# Rudder_-_Prototype_1.net
KiCad netlist of a schematic drawn in EAGLE
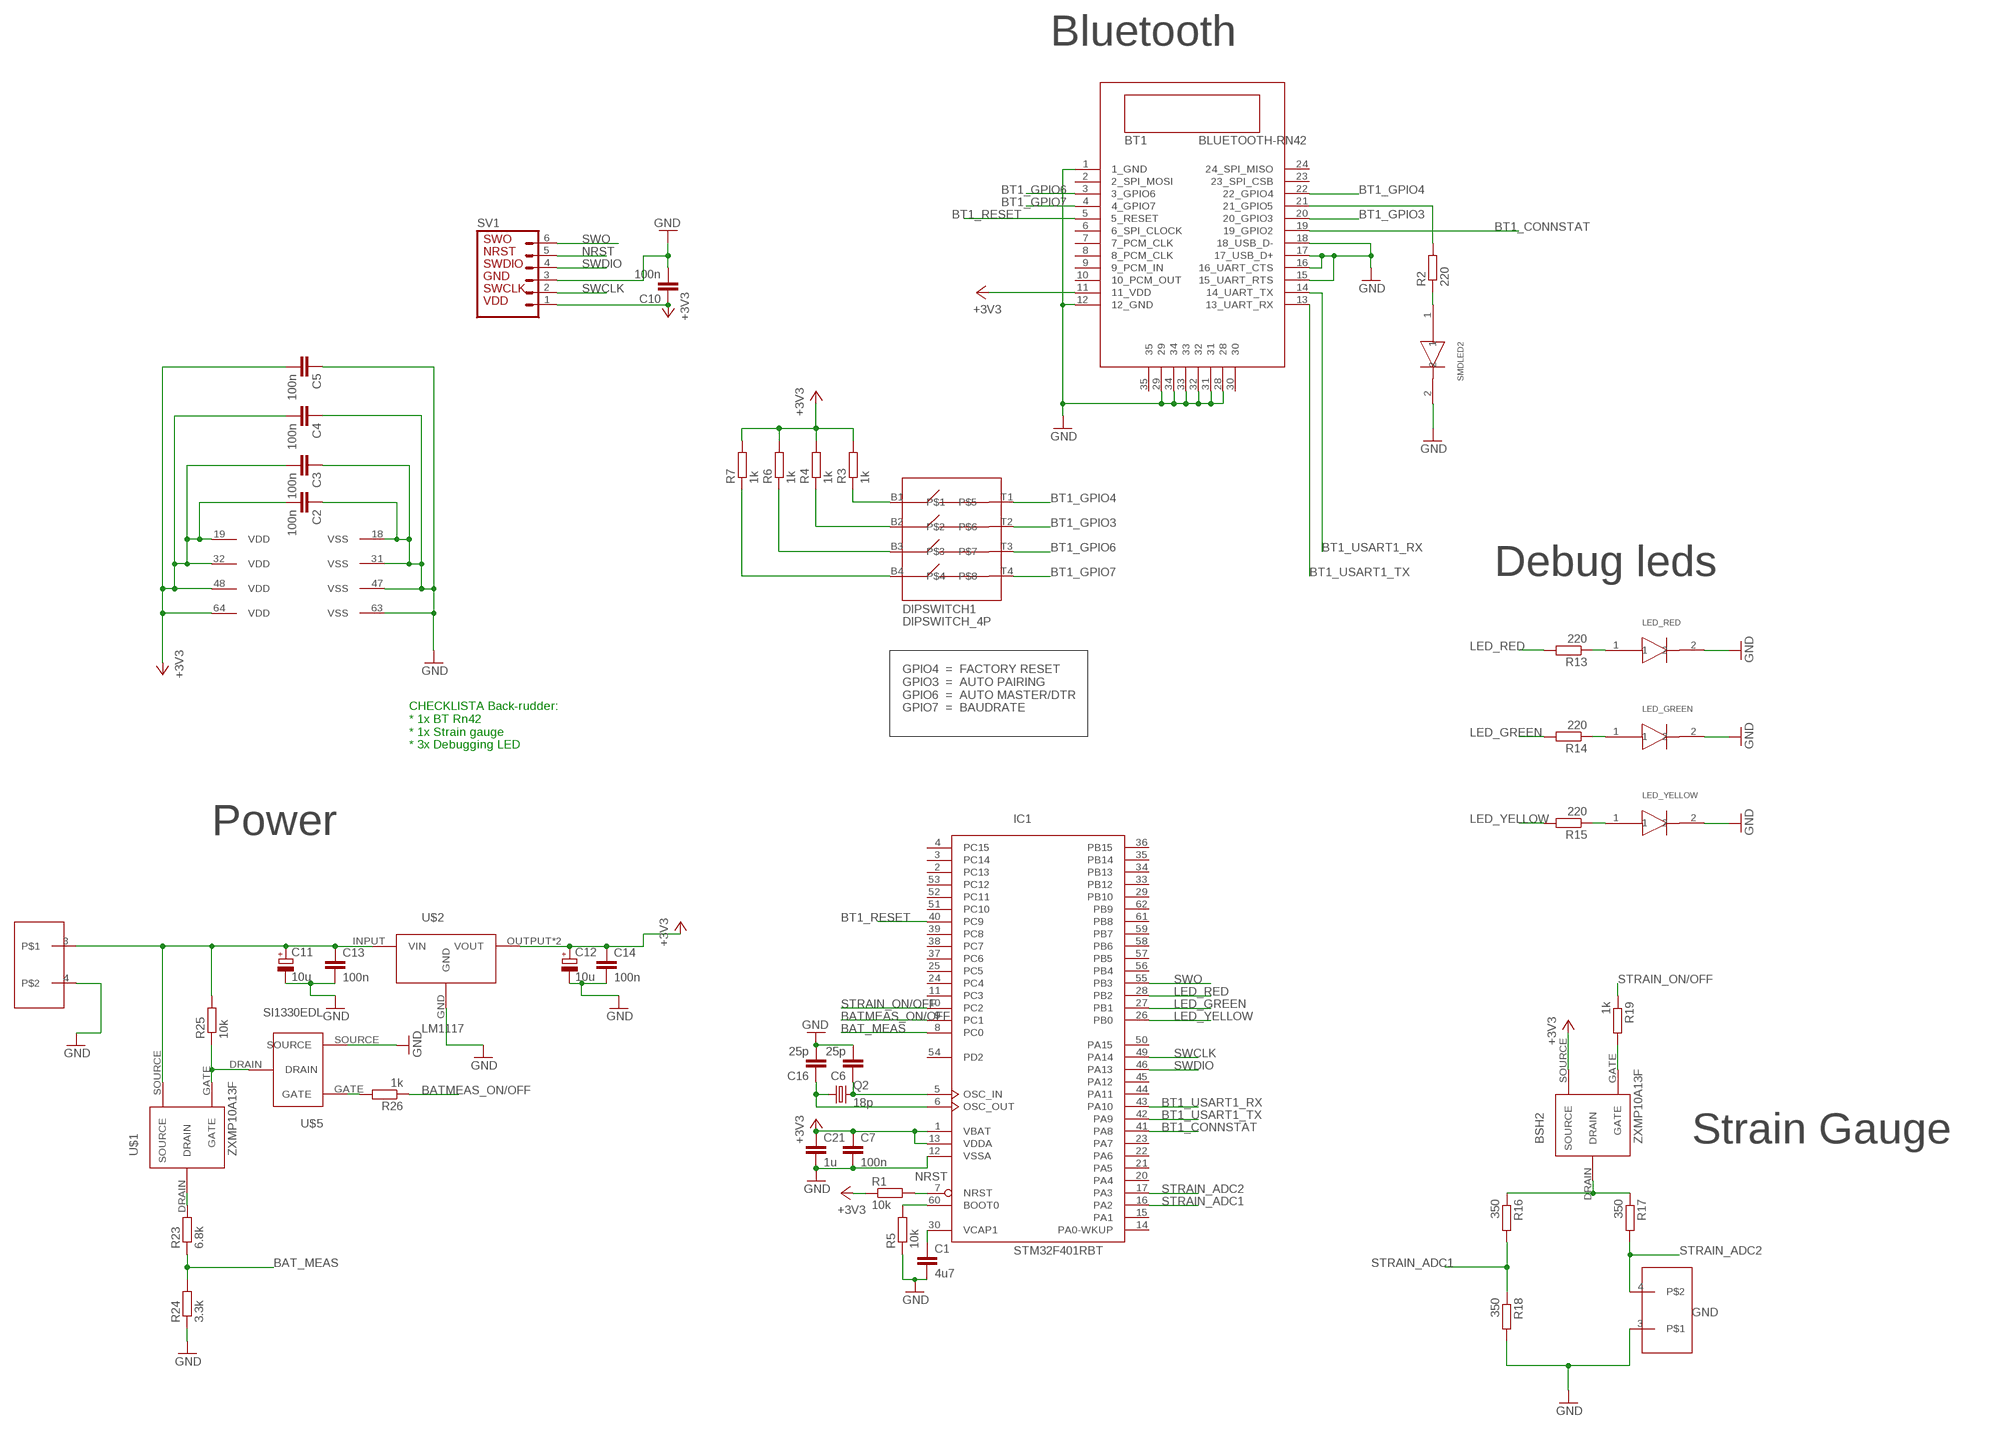
[diagram p0: schematic, sheet 1]

(export (version "E")
  (design (tool "Eeschema 10.0.6"))
  (components
    (comp (ref "BSH2")
      (value "ZXMP10A13F")
      (footprint "eagle-import:P-CHANNEL")
      (libsource (lib "eagle-import") (part "ZXMP10A13F"))
    )
    (comp (ref "BT1")
      (value "BLUETOOTH-RN42")
      (footprint "eagle-import:RN42")
      (libsource (lib "eagle-import") (part "BLUETOOTH-RN42"))
    )
    (comp (ref "C1")
      (value "4u7")
      (footprint "eagle-import:C0805")
      (libsource (lib "eagle-import") (part "C-EUC0805"))
    )
    (comp (ref "C2")
      (value "100n")
      (footprint "eagle-import:C0805")
      (libsource (lib "eagle-import") (part "C-EUC0805"))
    )
    (comp (ref "C3")
      (value "100n")
      (footprint "eagle-import:C0805")
      (libsource (lib "eagle-import") (part "C-EUC0805"))
    )
    (comp (ref "C4")
      (value "100n")
      (footprint "eagle-import:C0805")
      (libsource (lib "eagle-import") (part "C-EUC0805"))
    )
    (comp (ref "C5")
      (value "100n")
      (footprint "eagle-import:C0805")
      (libsource (lib "eagle-import") (part "C-EUC0805"))
    )
    (comp (ref "C6")
      (value "25p")
      (footprint "eagle-import:C0805")
      (libsource (lib "eagle-import") (part "C-EUC0805"))
    )
    (comp (ref "C7")
      (value "100n")
      (footprint "eagle-import:C0805")
      (libsource (lib "eagle-import") (part "C-EUC0805"))
    )
    (comp (ref "C10")
      (value "100n")
      (footprint "eagle-import:C0805")
      (libsource (lib "eagle-import") (part "C-EUC0805"))
    )
    (comp (ref "C11")
      (value "10u")
      (footprint "eagle-import:153CLV-0505")
      (libsource (lib "eagle-import") (part "CPOL-EU153CLV-0505"))
    )
    (comp (ref "C12")
      (value "10u")
      (footprint "eagle-import:153CLV-0505")
      (libsource (lib "eagle-import") (part "CPOL-EU153CLV-0505"))
    )
    (comp (ref "C13")
      (value "100n")
      (footprint "eagle-import:C0805")
      (libsource (lib "eagle-import") (part "C-EUC0805"))
    )
    (comp (ref "C14")
      (value "100n")
      (footprint "eagle-import:C0805")
      (libsource (lib "eagle-import") (part "C-EUC0805"))
    )
    (comp (ref "C16")
      (value "25p")
      (footprint "eagle-import:C0805")
      (libsource (lib "eagle-import") (part "C-EUC0805"))
    )
    (comp (ref "C21")
      (value "1u")
      (footprint "eagle-import:C0805")
      (libsource (lib "eagle-import") (part "C-EUC0805"))
    )
    (comp (ref "DIPSWITCH1")
      (value "DIPSWITCH_4P")
      (footprint "eagle-import:DIPSWITCH4P")
      (libsource (lib "eagle-import") (part "DIPSWITCH_4P"))
    )
    (comp (ref "IC1")
      (value "STM32F401RBT")
      (footprint "eagle-import:LQFP64")
      (libsource (lib "eagle-import") (part "STM32F401RTB"))
    )
    (comp (ref "LED_GREEN")
      (value "SMD_LED")
      (footprint "eagle-import:SMD_LED_CUSTOM")
      (libsource (lib "eagle-import") (part "SMD_LED"))
    )
    (comp (ref "LED_RED")
      (value "SMD_LED")
      (footprint "eagle-import:SMD_LED_CUSTOM")
      (libsource (lib "eagle-import") (part "SMD_LED"))
    )
    (comp (ref "LED_YELLOW")
      (value "SMD_LED")
      (footprint "eagle-import:SMD_LED_CUSTOM")
      (libsource (lib "eagle-import") (part "SMD_LED"))
    )
    (comp (ref "Q2")
      (value "18p")
      (footprint "eagle-import:HC49UP")
      (libsource (lib "eagle-import") (part "CRYSTALHC49UP"))
    )
    (comp (ref "R1")
      (value "10k")
      (footprint "eagle-import:R0805")
      (libsource (lib "eagle-import") (part "R-EU_R0805"))
    )
    (comp (ref "R2")
      (value "220")
      (footprint "eagle-import:R0805")
      (libsource (lib "eagle-import") (part "resistor_R-EU_R0805"))
    )
    (comp (ref "R3")
      (value "1k")
      (footprint "eagle-import:R0805")
      (libsource (lib "eagle-import") (part "resistor_R-EU_R0805"))
    )
    (comp (ref "R4")
      (value "1k")
      (footprint "eagle-import:R0805")
      (libsource (lib "eagle-import") (part "resistor_R-EU_R0805"))
    )
    (comp (ref "R5")
      (value "10k")
      (footprint "eagle-import:R0805")
      (libsource (lib "eagle-import") (part "R-EU_R0805"))
    )
    (comp (ref "R6")
      (value "1k")
      (footprint "eagle-import:R0805")
      (libsource (lib "eagle-import") (part "resistor_R-EU_R0805"))
    )
    (comp (ref "R7")
      (value "1k")
      (footprint "eagle-import:R0805")
      (libsource (lib "eagle-import") (part "resistor_R-EU_R0805"))
    )
    (comp (ref "R13")
      (value "220")
      (footprint "eagle-import:R0805")
      (libsource (lib "eagle-import") (part "resistor_R-EU_R0805"))
    )
    (comp (ref "R14")
      (value "220")
      (footprint "eagle-import:R0805")
      (libsource (lib "eagle-import") (part "resistor_R-EU_R0805"))
    )
    (comp (ref "R15")
      (value "220")
      (footprint "eagle-import:R0805")
      (libsource (lib "eagle-import") (part "resistor_R-EU_R0805"))
    )
    (comp (ref "R16")
      (value "350")
      (footprint "eagle-import:R0805")
      (libsource (lib "eagle-import") (part "R-EU_R0805"))
    )
    (comp (ref "R17")
      (value "350")
      (footprint "eagle-import:R0805")
      (libsource (lib "eagle-import") (part "R-EU_R0805"))
    )
    (comp (ref "R18")
      (value "350")
      (footprint "eagle-import:R0805")
      (libsource (lib "eagle-import") (part "R-EU_R0805"))
    )
    (comp (ref "R19")
      (value "1k")
      (footprint "eagle-import:R0805")
      (libsource (lib "eagle-import") (part "R-EU_R0805"))
    )
    (comp (ref "R23")
      (value "6.8k")
      (footprint "eagle-import:R0805")
      (libsource (lib "eagle-import") (part "R-EU_R0805"))
    )
    (comp (ref "R24")
      (value "3.3k")
      (footprint "eagle-import:R0805")
      (libsource (lib "eagle-import") (part "R-EU_R0805"))
    )
    (comp (ref "R25")
      (value "10k")
      (footprint "eagle-import:R0805")
      (libsource (lib "eagle-import") (part "R-EU_R0805"))
    )
    (comp (ref "R26")
      (value "1k")
      (footprint "eagle-import:R0805")
      (libsource (lib "eagle-import") (part "R-EU_R0805"))
    )
    (comp (ref "SKRUVPLINT_2P3")
      (value "SKRUVPLINT_2P")
      (footprint "eagle-import:SKRUVPLINT_2P")
      (libsource (lib "eagle-import") (part "SKRUVPLINT_2P"))
    )
    (comp (ref "SKRUVPLINT_2P5")
      (value "SKRUVPLINT_2P")
      (footprint "eagle-import:SKRUVPLINT_2P")
      (libsource (lib "eagle-import") (part "SKRUVPLINT_2P"))
    )
    (comp (ref "SMDLED2")
      (value "SMD_LED")
      (footprint "eagle-import:SMD_LED_CUSTOM")
      (libsource (lib "eagle-import") (part "SMD_LED"))
    )
    (comp (ref "SV1")
      (value "MA06-1")
      (footprint "eagle-import:MA06-1")
      (libsource (lib "eagle-import") (part "MA06-1"))
    )
    (comp (ref "U$1")
      (value "ZXMP10A13F")
      (footprint "eagle-import:P-CHANNEL")
      (libsource (lib "eagle-import") (part "ZXMP10A13F"))
    )
    (comp (ref "U$2")
      (value "LM1117")
      (footprint "eagle-import:SOT-223")
      (libsource (lib "eagle-import") (part "LM1117"))
    )
    (comp (ref "U$5")
      (value "SI1330EDL")
      (footprint "eagle-import:SOT-323")
      (libsource (lib "eagle-import") (part "SI1330EDL"))
    )
  )
  (nets
    (net (code "1") (name "+3V3") (class "Default")
      (node (ref "BSH2") (pin "SOURCE") (pinfunction "SOURCE_SOURCE") (pintype "bidirectional"))
      (node (ref "BT1") (pin "11") (pinfunction "11_VDD_11") (pintype "bidirectional"))
      (node (ref "C10") (pin "1") (pinfunction "1_1") (pintype "passive"))
      (node (ref "C12") (pin "+") (pinfunction "+_+") (pintype "passive"))
      (node (ref "C14") (pin "1") (pinfunction "1_1") (pintype "passive"))
      (node (ref "C2") (pin "2") (pinfunction "2_2") (pintype "passive"))
      (node (ref "C21") (pin "1") (pinfunction "1_1") (pintype "passive"))
      (node (ref "C3") (pin "2") (pinfunction "2_2") (pintype "passive"))
      (node (ref "C4") (pin "2") (pinfunction "2_2") (pintype "passive"))
      (node (ref "C5") (pin "2") (pinfunction "2_2") (pintype "passive"))
      (node (ref "C7") (pin "1") (pinfunction "1_1") (pintype "passive"))
      (node (ref "IC1") (pin "1") (pinfunction "VBAT_1") (pintype "power_in"))
      (node (ref "IC1") (pin "13") (pinfunction "VDDA_13") (pintype "power_in"))
      (node (ref "IC1") (pin "19") (pinfunction "VDD_19") (pintype "power_in"))
      (node (ref "IC1") (pin "32") (pinfunction "VDD_32") (pintype "power_in"))
      (node (ref "IC1") (pin "48") (pinfunction "VDD_48") (pintype "power_in"))
      (node (ref "IC1") (pin "64") (pinfunction "VDD_64") (pintype "power_in"))
      (node (ref "R1") (pin "1") (pinfunction "1_1") (pintype "passive"))
      (node (ref "R3") (pin "2") (pinfunction "2_2") (pintype "passive"))
      (node (ref "R4") (pin "2") (pinfunction "2_2") (pintype "passive"))
      (node (ref "R6") (pin "2") (pinfunction "2_2") (pintype "passive"))
      (node (ref "R7") (pin "2") (pinfunction "2_2") (pintype "passive"))
      (node (ref "SV1") (pin "1") (pinfunction "1_1") (pintype "passive"))
      (node (ref "U$2") (pin "OUTPUT") (pinfunction "VOUT_OUTPUT") (pintype "bidirectional"))
      (node (ref "U$2") (pin "VOUT") (pinfunction "VOUT_VOUT") (pintype "bidirectional"))
    )
    (net (code "2") (name "/BATMEAS_ON{slash}OFF") (class "Default")
      (node (ref "IC1") (pin "9") (pinfunction "PC1_9") (pintype "bidirectional"))
      (node (ref "R26") (pin "1") (pinfunction "1_1") (pintype "passive"))
    )
    (net (code "3") (name "/BAT_MEAS") (class "Default")
      (node (ref "IC1") (pin "8") (pinfunction "PC0_8") (pintype "bidirectional"))
      (node (ref "R23") (pin "1") (pinfunction "1_1") (pintype "passive"))
      (node (ref "R24") (pin "2") (pinfunction "2_2") (pintype "passive"))
    )
    (net (code "4") (name "/BT1_CONNSTAT") (class "Default")
      (node (ref "BT1") (pin "19") (pinfunction "19_GPIO2_19") (pintype "bidirectional"))
      (node (ref "IC1") (pin "41") (pinfunction "PA8_41") (pintype "bidirectional"))
    )
    (net (code "5") (name "/BT1_GPIO3") (class "Default")
      (node (ref "BT1") (pin "20") (pinfunction "20_GPIO3_20") (pintype "bidirectional"))
      (node (ref "DIPSWITCH1") (pin "T2") (pinfunction "P$6_T2") (pintype "bidirectional"))
    )
    (net (code "6") (name "/BT1_GPIO4") (class "Default")
      (node (ref "BT1") (pin "22") (pinfunction "22_GPIO4_22") (pintype "bidirectional"))
      (node (ref "DIPSWITCH1") (pin "T1") (pinfunction "P$5_T1") (pintype "bidirectional"))
    )
    (net (code "7") (name "/BT1_GPIO6") (class "Default")
      (node (ref "BT1") (pin "3") (pinfunction "3_GPIO6_3") (pintype "bidirectional"))
      (node (ref "DIPSWITCH1") (pin "T3") (pinfunction "P$7_T3") (pintype "bidirectional"))
    )
    (net (code "8") (name "/BT1_GPIO7") (class "Default")
      (node (ref "BT1") (pin "4") (pinfunction "4_GPIO7_4") (pintype "bidirectional"))
      (node (ref "DIPSWITCH1") (pin "T4") (pinfunction "P$8_T4") (pintype "bidirectional"))
    )
    (net (code "9") (name "/BT1_RESET") (class "Default")
      (node (ref "BT1") (pin "5") (pinfunction "5_RESET_5") (pintype "bidirectional"))
      (node (ref "IC1") (pin "40") (pinfunction "PC9_40") (pintype "bidirectional"))
    )
    (net (code "10") (name "/BT1_USART1_RX") (class "Default")
      (node (ref "BT1") (pin "14") (pinfunction "14_UART_TX_14") (pintype "bidirectional"))
      (node (ref "IC1") (pin "43") (pinfunction "PA10_43") (pintype "bidirectional"))
    )
    (net (code "11") (name "/BT1_USART1_TX") (class "Default")
      (node (ref "BT1") (pin "13") (pinfunction "13_UART_RX_13") (pintype "bidirectional"))
      (node (ref "IC1") (pin "42") (pinfunction "PA9_42") (pintype "bidirectional"))
    )
    (net (code "12") (name "/LED_GREEN") (class "Default")
      (node (ref "IC1") (pin "27") (pinfunction "PB1_27") (pintype "bidirectional"))
      (node (ref "R14") (pin "2") (pinfunction "2_2") (pintype "passive"))
    )
    (net (code "13") (name "/LED_RED") (class "Default")
      (node (ref "IC1") (pin "28") (pinfunction "PB2_28") (pintype "bidirectional"))
      (node (ref "R13") (pin "2") (pinfunction "2_2") (pintype "passive"))
    )
    (net (code "14") (name "/LED_YELLOW") (class "Default")
      (node (ref "IC1") (pin "26") (pinfunction "PB0_26") (pintype "bidirectional"))
      (node (ref "R15") (pin "2") (pinfunction "2_2") (pintype "passive"))
    )
    (net (code "15") (name "/NRST") (class "Default")
      (node (ref "IC1") (pin "7") (pinfunction "NRST_7") (pintype "bidirectional"))
      (node (ref "R1") (pin "2") (pinfunction "2_2") (pintype "passive"))
      (node (ref "SV1") (pin "5") (pinfunction "5_5") (pintype "passive"))
    )
    (net (code "16") (name "/STRAIN_ADC1") (class "Default")
      (node (ref "IC1") (pin "16") (pinfunction "PA2_16") (pintype "bidirectional"))
      (node (ref "R16") (pin "2") (pinfunction "2_2") (pintype "passive"))
      (node (ref "R18") (pin "1") (pinfunction "1_1") (pintype "passive"))
    )
    (net (code "17") (name "/STRAIN_ADC2") (class "Default")
      (node (ref "IC1") (pin "17") (pinfunction "PA3_17") (pintype "bidirectional"))
      (node (ref "R17") (pin "2") (pinfunction "2_2") (pintype "passive"))
      (node (ref "SKRUVPLINT_2P3") (pin "4") (pinfunction "P$2_4") (pintype "bidirectional"))
    )
    (net (code "18") (name "/STRAIN_ON{slash}OFF") (class "Default")
      (node (ref "IC1") (pin "10") (pinfunction "PC2_10") (pintype "bidirectional"))
      (node (ref "R19") (pin "1") (pinfunction "1_1") (pintype "passive"))
    )
    (net (code "19") (name "/SWCLK") (class "Default")
      (node (ref "IC1") (pin "49") (pinfunction "PA14_49") (pintype "bidirectional"))
      (node (ref "SV1") (pin "2") (pinfunction "2_2") (pintype "passive"))
    )
    (net (code "20") (name "/SWDIO") (class "Default")
      (node (ref "IC1") (pin "46") (pinfunction "PA13_46") (pintype "bidirectional"))
      (node (ref "SV1") (pin "4") (pinfunction "4_4") (pintype "passive"))
    )
    (net (code "21") (name "/SWO") (class "Default")
      (node (ref "IC1") (pin "55") (pinfunction "PB3_55") (pintype "bidirectional"))
      (node (ref "SV1") (pin "6") (pinfunction "6_6") (pintype "passive"))
    )
    (net (code "22") (name "GND") (class "Default")
      (node (ref "BT1") (pin "1") (pinfunction "1_GND_1") (pintype "bidirectional"))
      (node (ref "BT1") (pin "12") (pinfunction "12_GND_12") (pintype "bidirectional"))
      (node (ref "BT1") (pin "15") (pinfunction "15_UART_RTS_15") (pintype "bidirectional"))
      (node (ref "BT1") (pin "16") (pinfunction "16_UART_CTS_16") (pintype "bidirectional"))
      (node (ref "BT1") (pin "17") (pinfunction "17_USB_D+_17") (pintype "bidirectional"))
      (node (ref "BT1") (pin "18") (pinfunction "18_USB_D-_18") (pintype "bidirectional"))
      (node (ref "BT1") (pin "28") (pinfunction "28_28") (pintype "bidirectional"))
      (node (ref "BT1") (pin "29") (pinfunction "29_29") (pintype "bidirectional"))
      (node (ref "BT1") (pin "31") (pinfunction "31_31") (pintype "bidirectional"))
      (node (ref "BT1") (pin "32") (pinfunction "32_32") (pintype "bidirectional"))
      (node (ref "BT1") (pin "33") (pinfunction "33_33") (pintype "bidirectional"))
      (node (ref "BT1") (pin "34") (pinfunction "34_34") (pintype "bidirectional"))
      (node (ref "C1") (pin "2") (pinfunction "2_2") (pintype "passive"))
      (node (ref "C10") (pin "2") (pinfunction "2_2") (pintype "passive"))
      (node (ref "C11") (pin "-") (pinfunction "-_-") (pintype "passive"))
      (node (ref "C12") (pin "-") (pinfunction "-_-") (pintype "passive"))
      (node (ref "C13") (pin "2") (pinfunction "2_2") (pintype "passive"))
      (node (ref "C14") (pin "2") (pinfunction "2_2") (pintype "passive"))
      (node (ref "C16") (pin "2") (pinfunction "2_2") (pintype "passive"))
      (node (ref "C2") (pin "1") (pinfunction "1_1") (pintype "passive"))
      (node (ref "C21") (pin "2") (pinfunction "2_2") (pintype "passive"))
      (node (ref "C3") (pin "1") (pinfunction "1_1") (pintype "passive"))
      (node (ref "C4") (pin "1") (pinfunction "1_1") (pintype "passive"))
      (node (ref "C5") (pin "1") (pinfunction "1_1") (pintype "passive"))
      (node (ref "C6") (pin "2") (pinfunction "2_2") (pintype "passive"))
      (node (ref "C7") (pin "2") (pinfunction "2_2") (pintype "passive"))
      (node (ref "IC1") (pin "12") (pinfunction "VSSA_12") (pintype "power_in"))
      (node (ref "IC1") (pin "18") (pinfunction "VSS_18") (pintype "power_in"))
      (node (ref "IC1") (pin "31") (pinfunction "VSS_31") (pintype "power_in"))
      (node (ref "IC1") (pin "47") (pinfunction "VSS_47") (pintype "power_in"))
      (node (ref "IC1") (pin "63") (pinfunction "VSS_63") (pintype "power_in"))
      (node (ref "LED_GREEN") (pin "2") (pinfunction "2_2") (pintype "bidirectional"))
      (node (ref "LED_RED") (pin "2") (pinfunction "2_2") (pintype "bidirectional"))
      (node (ref "LED_YELLOW") (pin "2") (pinfunction "2_2") (pintype "bidirectional"))
      (node (ref "R18") (pin "2") (pinfunction "2_2") (pintype "passive"))
      (node (ref "R24") (pin "1") (pinfunction "1_1") (pintype "passive"))
      (node (ref "R5") (pin "1") (pinfunction "1_1") (pintype "passive"))
      (node (ref "SKRUVPLINT_2P3") (pin "3") (pinfunction "P$1_3") (pintype "bidirectional"))
      (node (ref "SKRUVPLINT_2P5") (pin "4") (pinfunction "P$2_4") (pintype "bidirectional"))
      (node (ref "SMDLED2") (pin "2") (pinfunction "2_2") (pintype "bidirectional"))
      (node (ref "SV1") (pin "3") (pinfunction "3_3") (pintype "passive"))
      (node (ref "U$2") (pin "GND") (pinfunction "GND_GND") (pintype "bidirectional"))
      (node (ref "U$5") (pin "SOURCE") (pinfunction "SOURCE_SOURCE") (pintype "bidirectional"))
    )
    (net (code "23") (name "Net-(BSH2-PadDRAIN)") (class "Default")
      (node (ref "BSH2") (pin "DRAIN") (pinfunction "DRAIN_DRAIN") (pintype "bidirectional"))
      (node (ref "R16") (pin "1") (pinfunction "1_1") (pintype "passive"))
      (node (ref "R17") (pin "1") (pinfunction "1_1") (pintype "passive"))
    )
    (net (code "24") (name "Net-(BSH2-PadGATE)") (class "Default")
      (node (ref "BSH2") (pin "GATE") (pinfunction "GATE_GATE") (pintype "bidirectional"))
      (node (ref "R19") (pin "2") (pinfunction "2_2") (pintype "passive"))
    )
    (net (code "25") (name "Net-(BT1-21_GPIO5)") (class "Default")
      (node (ref "BT1") (pin "21") (pinfunction "21_GPIO5_21") (pintype "bidirectional"))
      (node (ref "R2") (pin "2") (pinfunction "2_2") (pintype "passive"))
    )
    (net (code "26") (name "Net-(DIPSWITCH1-P$1)") (class "Default")
      (node (ref "DIPSWITCH1") (pin "B1") (pinfunction "P$1_B1") (pintype "bidirectional"))
      (node (ref "R3") (pin "1") (pinfunction "1_1") (pintype "passive"))
    )
    (net (code "27") (name "Net-(DIPSWITCH1-P$2)") (class "Default")
      (node (ref "DIPSWITCH1") (pin "B2") (pinfunction "P$2_B2") (pintype "bidirectional"))
      (node (ref "R4") (pin "1") (pinfunction "1_1") (pintype "passive"))
    )
    (net (code "28") (name "Net-(DIPSWITCH1-P$3)") (class "Default")
      (node (ref "DIPSWITCH1") (pin "B3") (pinfunction "P$3_B3") (pintype "bidirectional"))
      (node (ref "R6") (pin "1") (pinfunction "1_1") (pintype "passive"))
    )
    (net (code "29") (name "Net-(DIPSWITCH1-P$4)") (class "Default")
      (node (ref "DIPSWITCH1") (pin "B4") (pinfunction "P$4_B4") (pintype "bidirectional"))
      (node (ref "R7") (pin "1") (pinfunction "1_1") (pintype "passive"))
    )
    (net (code "30") (name "Net-(IC1A-BOOT0)") (class "Default")
      (node (ref "IC1") (pin "60") (pinfunction "BOOT0_60") (pintype "input"))
      (node (ref "R5") (pin "2") (pinfunction "2_2") (pintype "passive"))
    )
    (net (code "31") (name "Net-(IC1A-OSC_IN)") (class "Default")
      (node (ref "C6") (pin "1") (pinfunction "1_1") (pintype "passive"))
      (node (ref "IC1") (pin "5") (pinfunction "OSC_IN_5") (pintype "bidirectional"))
      (node (ref "Q2") (pin "2") (pinfunction "2_2") (pintype "passive"))
    )
    (net (code "32") (name "Net-(IC1A-OSC_OUT)") (class "Default")
      (node (ref "C16") (pin "1") (pinfunction "1_1") (pintype "passive"))
      (node (ref "IC1") (pin "6") (pinfunction "OSC_OUT_6") (pintype "bidirectional"))
      (node (ref "Q2") (pin "1") (pinfunction "1_1") (pintype "passive"))
    )
    (net (code "33") (name "Net-(IC1A-VCAP1)") (class "Default")
      (node (ref "C1") (pin "1") (pinfunction "1_1") (pintype "passive"))
      (node (ref "IC1") (pin "30") (pinfunction "VCAP1_30") (pintype "power_in"))
    )
    (net (code "34") (name "Net-(LED_GREEN-Pad1)") (class "Default")
      (node (ref "LED_GREEN") (pin "1") (pinfunction "1_1") (pintype "bidirectional"))
      (node (ref "R14") (pin "1") (pinfunction "1_1") (pintype "passive"))
    )
    (net (code "35") (name "Net-(LED_RED-Pad1)") (class "Default")
      (node (ref "LED_RED") (pin "1") (pinfunction "1_1") (pintype "bidirectional"))
      (node (ref "R13") (pin "1") (pinfunction "1_1") (pintype "passive"))
    )
    (net (code "36") (name "Net-(LED_YELLOW-Pad1)") (class "Default")
      (node (ref "LED_YELLOW") (pin "1") (pinfunction "1_1") (pintype "bidirectional"))
      (node (ref "R15") (pin "1") (pinfunction "1_1") (pintype "passive"))
    )
    (net (code "37") (name "Net-(R2-Pad1)") (class "Default")
      (node (ref "R2") (pin "1") (pinfunction "1_1") (pintype "passive"))
      (node (ref "SMDLED2") (pin "1") (pinfunction "1_1") (pintype "bidirectional"))
    )
    (net (code "38") (name "Net-(R23-Pad2)") (class "Default")
      (node (ref "R23") (pin "2") (pinfunction "2_2") (pintype "passive"))
      (node (ref "U$1") (pin "DRAIN") (pinfunction "DRAIN_DRAIN") (pintype "bidirectional"))
    )
    (net (code "39") (name "Net-(R25-Pad1)") (class "Default")
      (node (ref "R25") (pin "1") (pinfunction "1_1") (pintype "passive"))
      (node (ref "U$1") (pin "GATE") (pinfunction "GATE_GATE") (pintype "bidirectional"))
      (node (ref "U$5") (pin "DRAIN") (pinfunction "DRAIN_DRAIN") (pintype "bidirectional"))
    )
    (net (code "40") (name "Net-(R26-Pad2)") (class "Default")
      (node (ref "R26") (pin "2") (pinfunction "2_2") (pintype "passive"))
      (node (ref "U$5") (pin "GATE") (pinfunction "GATE_GATE") (pintype "bidirectional"))
    )
    (net (code "41") (name "Net-(SKRUVPLINT_2P5-P$1)") (class "Default")
      (node (ref "C11") (pin "+") (pinfunction "+_+") (pintype "passive"))
      (node (ref "C13") (pin "1") (pinfunction "1_1") (pintype "passive"))
      (node (ref "R25") (pin "2") (pinfunction "2_2") (pintype "passive"))
      (node (ref "SKRUVPLINT_2P5") (pin "3") (pinfunction "P$1_3") (pintype "bidirectional"))
      (node (ref "U$1") (pin "SOURCE") (pinfunction "SOURCE_SOURCE") (pintype "bidirectional"))
      (node (ref "U$2") (pin "INPUT") (pinfunction "VIN_INPUT") (pintype "bidirectional"))
    )
    (net (code "42") (name "unconnected-(BT1-2_SPI_MOSI-Pad2)") (class "Default")
      (node (ref "BT1") (pin "2") (pinfunction "2_SPI_MOSI_2") (pintype "bidirectional"))
    )
    (net (code "43") (name "unconnected-(BT1-6_SPI_CLOCK-Pad6)") (class "Default")
      (node (ref "BT1") (pin "6") (pinfunction "6_SPI_CLOCK_6") (pintype "bidirectional"))
    )
    (net (code "44") (name "unconnected-(BT1-7_PCM_CLK-Pad7)") (class "Default")
      (node (ref "BT1") (pin "7") (pinfunction "7_PCM_CLK_7") (pintype "bidirectional"))
    )
    (net (code "45") (name "unconnected-(BT1-8_PCM_CLK-Pad8)") (class "Default")
      (node (ref "BT1") (pin "8") (pinfunction "8_PCM_CLK_8") (pintype "bidirectional"))
    )
    (net (code "46") (name "unconnected-(BT1-9_PCM_IN-Pad9)") (class "Default")
      (node (ref "BT1") (pin "9") (pinfunction "9_PCM_IN_9") (pintype "bidirectional"))
    )
    (net (code "47") (name "unconnected-(BT1-10_PCM_OUT-Pad10)") (class "Default")
      (node (ref "BT1") (pin "10") (pinfunction "10_PCM_OUT_10") (pintype "bidirectional"))
    )
    (net (code "48") (name "unconnected-(BT1-23_SPI_CSB-Pad23)") (class "Default")
      (node (ref "BT1") (pin "23") (pinfunction "23_SPI_CSB_23") (pintype "bidirectional"))
    )
    (net (code "49") (name "unconnected-(BT1-24_SPI_MISO-Pad24)") (class "Default")
      (node (ref "BT1") (pin "24") (pinfunction "24_SPI_MISO_24") (pintype "bidirectional"))
    )
    (net (code "50") (name "unconnected-(BT1-Pad30)") (class "Default")
      (node (ref "BT1") (pin "30") (pinfunction "30_30") (pintype "bidirectional"))
    )
    (net (code "51") (name "unconnected-(BT1-Pad35)") (class "Default")
      (node (ref "BT1") (pin "35") (pinfunction "35_35") (pintype "bidirectional"))
    )
    (net (code "52") (name "unconnected-(IC1A-PA0-WKUP-Pad14)") (class "Default")
      (node (ref "IC1") (pin "14") (pinfunction "PA0-WKUP_14") (pintype "bidirectional"))
    )
    (net (code "53") (name "unconnected-(IC1A-PA1-Pad15)") (class "Default")
      (node (ref "IC1") (pin "15") (pinfunction "PA1_15") (pintype "bidirectional"))
    )
    (net (code "54") (name "unconnected-(IC1A-PA4-Pad20)") (class "Default")
      (node (ref "IC1") (pin "20") (pinfunction "PA4_20") (pintype "bidirectional"))
    )
    (net (code "55") (name "unconnected-(IC1A-PA5-Pad21)") (class "Default")
      (node (ref "IC1") (pin "21") (pinfunction "PA5_21") (pintype "bidirectional"))
    )
    (net (code "56") (name "unconnected-(IC1A-PA6-Pad22)") (class "Default")
      (node (ref "IC1") (pin "22") (pinfunction "PA6_22") (pintype "bidirectional"))
    )
    (net (code "57") (name "unconnected-(IC1A-PA7-Pad23)") (class "Default")
      (node (ref "IC1") (pin "23") (pinfunction "PA7_23") (pintype "bidirectional"))
    )
    (net (code "58") (name "unconnected-(IC1A-PA11-Pad44)") (class "Default")
      (node (ref "IC1") (pin "44") (pinfunction "PA11_44") (pintype "bidirectional"))
    )
    (net (code "59") (name "unconnected-(IC1A-PA12-Pad45)") (class "Default")
      (node (ref "IC1") (pin "45") (pinfunction "PA12_45") (pintype "bidirectional"))
    )
    (net (code "60") (name "unconnected-(IC1A-PA15-Pad50)") (class "Default")
      (node (ref "IC1") (pin "50") (pinfunction "PA15_50") (pintype "bidirectional"))
    )
    (net (code "61") (name "unconnected-(IC1A-PB4-Pad56)") (class "Default")
      (node (ref "IC1") (pin "56") (pinfunction "PB4_56") (pintype "bidirectional"))
    )
    (net (code "62") (name "unconnected-(IC1A-PB5-Pad57)") (class "Default")
      (node (ref "IC1") (pin "57") (pinfunction "PB5_57") (pintype "bidirectional"))
    )
    (net (code "63") (name "unconnected-(IC1A-PB6-Pad58)") (class "Default")
      (node (ref "IC1") (pin "58") (pinfunction "PB6_58") (pintype "bidirectional"))
    )
    (net (code "64") (name "unconnected-(IC1A-PB7-Pad59)") (class "Default")
      (node (ref "IC1") (pin "59") (pinfunction "PB7_59") (pintype "bidirectional"))
    )
    (net (code "65") (name "unconnected-(IC1A-PB8-Pad61)") (class "Default")
      (node (ref "IC1") (pin "61") (pinfunction "PB8_61") (pintype "bidirectional"))
    )
    (net (code "66") (name "unconnected-(IC1A-PB9-Pad62)") (class "Default")
      (node (ref "IC1") (pin "62") (pinfunction "PB9_62") (pintype "bidirectional"))
    )
    (net (code "67") (name "unconnected-(IC1A-PB10-Pad29)") (class "Default")
      (node (ref "IC1") (pin "29") (pinfunction "PB10_29") (pintype "bidirectional"))
    )
    (net (code "68") (name "unconnected-(IC1A-PB12-Pad33)") (class "Default")
      (node (ref "IC1") (pin "33") (pinfunction "PB12_33") (pintype "bidirectional"))
    )
    (net (code "69") (name "unconnected-(IC1A-PB13-Pad34)") (class "Default")
      (node (ref "IC1") (pin "34") (pinfunction "PB13_34") (pintype "bidirectional"))
    )
    (net (code "70") (name "unconnected-(IC1A-PB14-Pad35)") (class "Default")
      (node (ref "IC1") (pin "35") (pinfunction "PB14_35") (pintype "bidirectional"))
    )
    (net (code "71") (name "unconnected-(IC1A-PB15-Pad36)") (class "Default")
      (node (ref "IC1") (pin "36") (pinfunction "PB15_36") (pintype "bidirectional"))
    )
    (net (code "72") (name "unconnected-(IC1A-PC3-Pad11)") (class "Default")
      (node (ref "IC1") (pin "11") (pinfunction "PC3_11") (pintype "bidirectional"))
    )
    (net (code "73") (name "unconnected-(IC1A-PC4-Pad24)") (class "Default")
      (node (ref "IC1") (pin "24") (pinfunction "PC4_24") (pintype "bidirectional"))
    )
    (net (code "74") (name "unconnected-(IC1A-PC5-Pad25)") (class "Default")
      (node (ref "IC1") (pin "25") (pinfunction "PC5_25") (pintype "bidirectional"))
    )
    (net (code "75") (name "unconnected-(IC1A-PC6-Pad37)") (class "Default")
      (node (ref "IC1") (pin "37") (pinfunction "PC6_37") (pintype "bidirectional"))
    )
    (net (code "76") (name "unconnected-(IC1A-PC7-Pad38)") (class "Default")
      (node (ref "IC1") (pin "38") (pinfunction "PC7_38") (pintype "bidirectional"))
    )
    (net (code "77") (name "unconnected-(IC1A-PC8-Pad39)") (class "Default")
      (node (ref "IC1") (pin "39") (pinfunction "PC8_39") (pintype "bidirectional"))
    )
    (net (code "78") (name "unconnected-(IC1A-PC10-Pad51)") (class "Default")
      (node (ref "IC1") (pin "51") (pinfunction "PC10_51") (pintype "bidirectional"))
    )
    (net (code "79") (name "unconnected-(IC1A-PC11-Pad52)") (class "Default")
      (node (ref "IC1") (pin "52") (pinfunction "PC11_52") (pintype "bidirectional"))
    )
    (net (code "80") (name "unconnected-(IC1A-PC12-Pad53)") (class "Default")
      (node (ref "IC1") (pin "53") (pinfunction "PC12_53") (pintype "bidirectional"))
    )
    (net (code "81") (name "unconnected-(IC1A-PC13-Pad2)") (class "Default")
      (node (ref "IC1") (pin "2") (pinfunction "PC13_2") (pintype "bidirectional"))
    )
    (net (code "82") (name "unconnected-(IC1A-PC14-Pad3)") (class "Default")
      (node (ref "IC1") (pin "3") (pinfunction "PC14_3") (pintype "bidirectional"))
    )
    (net (code "83") (name "unconnected-(IC1A-PC15-Pad4)") (class "Default")
      (node (ref "IC1") (pin "4") (pinfunction "PC15_4") (pintype "bidirectional"))
    )
    (net (code "84") (name "unconnected-(IC1A-PD2-Pad54)") (class "Default")
      (node (ref "IC1") (pin "54") (pinfunction "PD2_54") (pintype "bidirectional"))
    )
  )
)
